# MainBoard.net
KiCad netlist of a schematic drawn in EAGLE
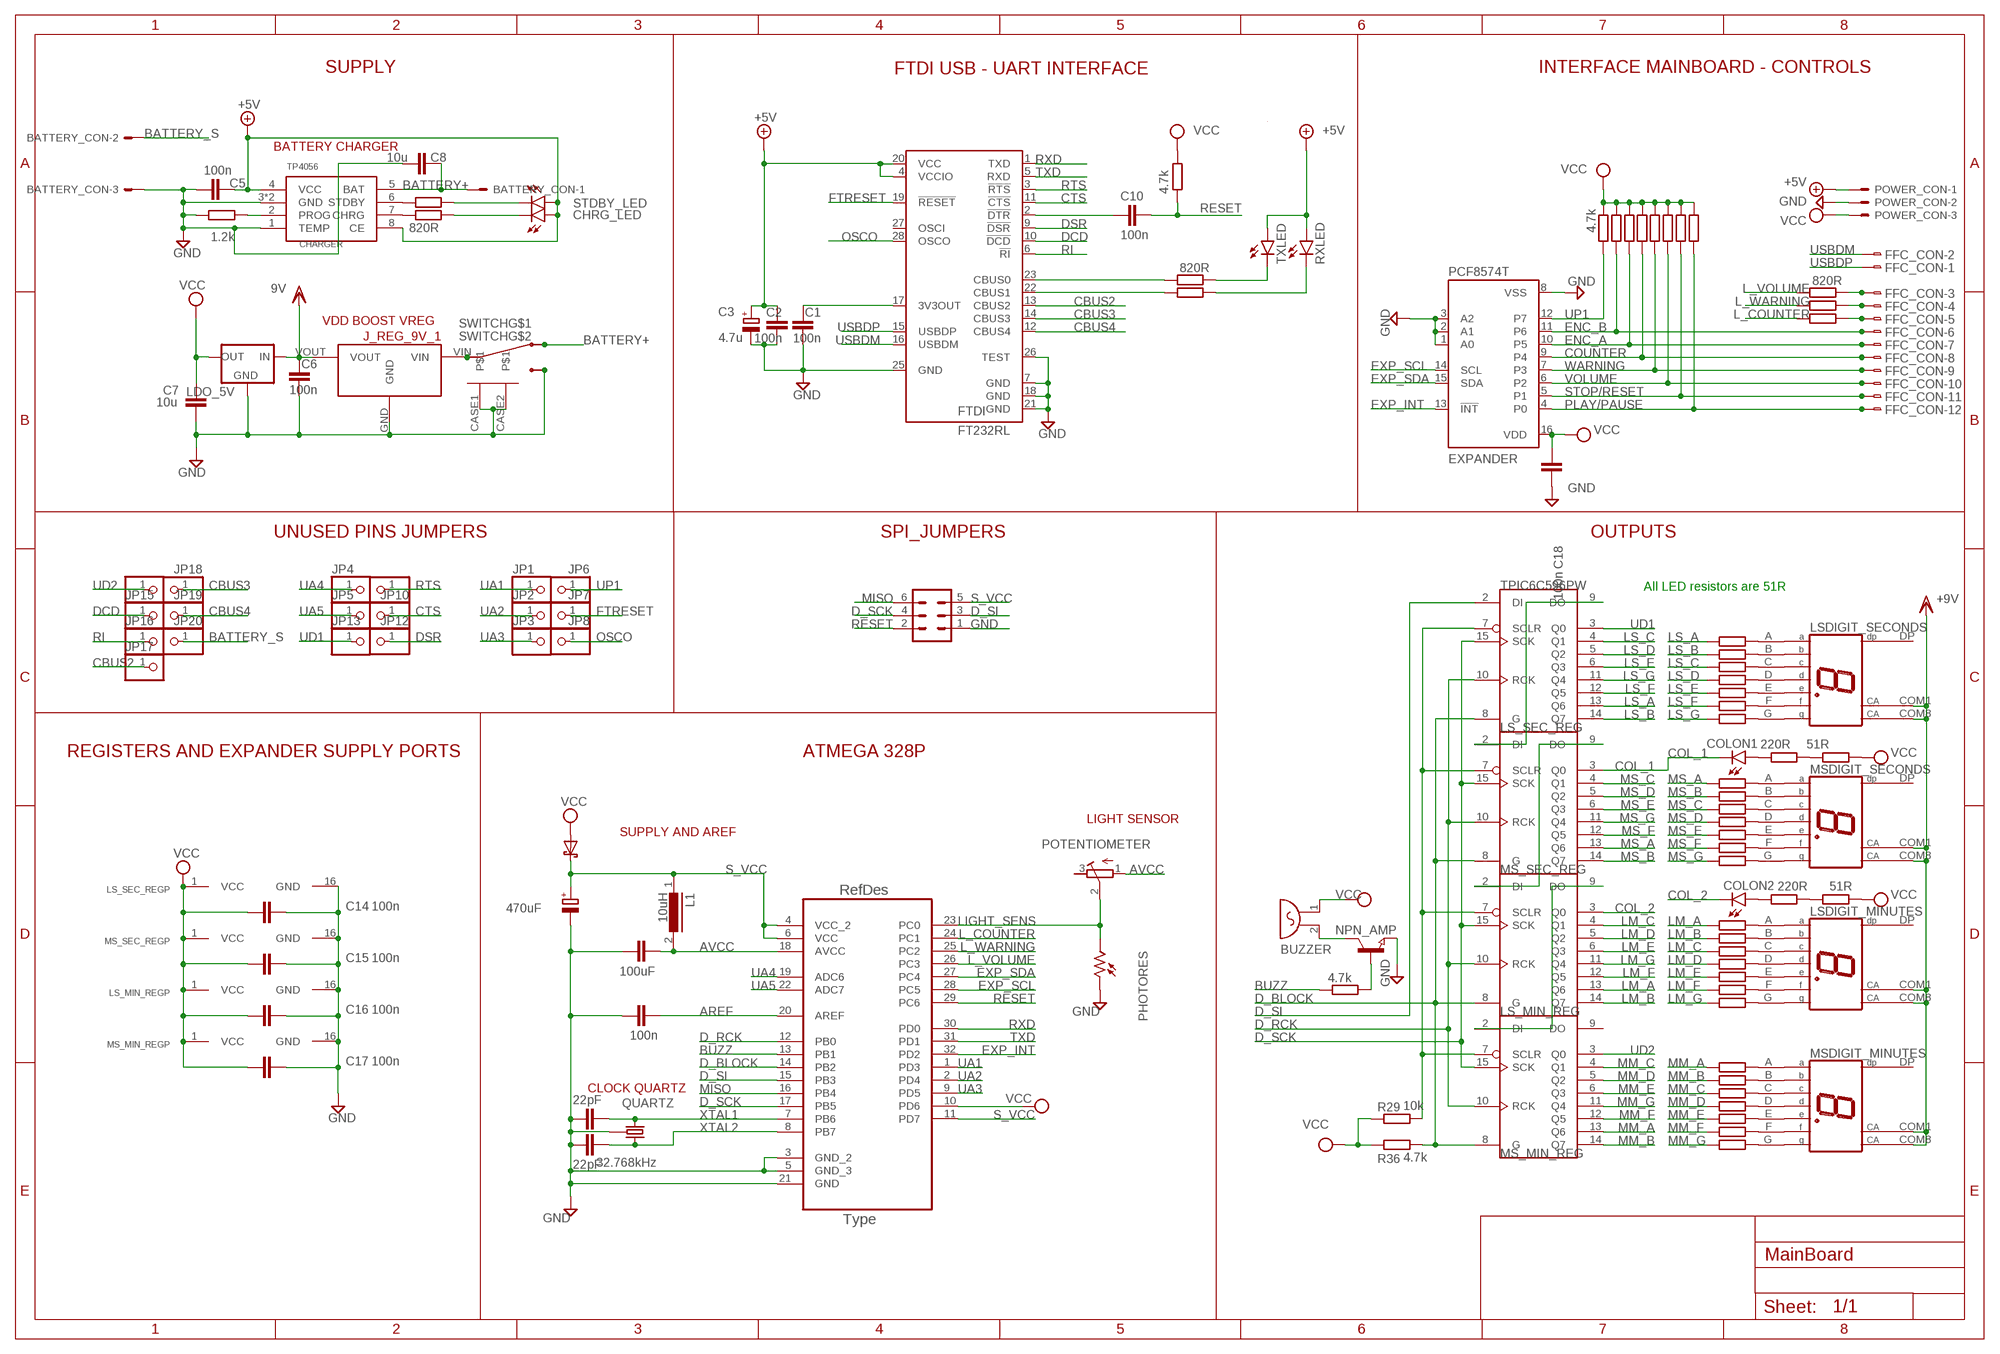
[diagram p0: schematic, sheet 1]

(export (version "E")
  (design (tool "Eeschema 10.0.6"))
  (components
    (comp (ref "ATMEGA328P")
      (value "ATMEGA328P-AU")
      (footprint "eagle-import:QFP80P900X900X120-32N")
      (libsource (lib "eagle-import") (part "ATMEGA328P-AU"))
    )
    (comp (ref "BATTERY_CON")
      (value "JST-XH-03-PIN-LONG-PAD")
      (footprint "eagle-import:JST-XH-03-PACKAGE-LONG-PAD")
      (libsource (lib "eagle-import") (part "JST-XH-03-PIN-LONG-PAD"))
    )
    (comp (ref "BUZZER")
      (value "F/HGP")
      (footprint "eagle-import:F_HGP")
      (libsource (lib "eagle-import") (part "F/HGP"))
    )
    (comp (ref "C1")
      (value "100n")
      (footprint "eagle-import:C0603")
      (libsource (lib "eagle-import") (part "C-EUC0603"))
    )
    (comp (ref "C2")
      (value "100n")
      (footprint "eagle-import:C0603")
      (libsource (lib "eagle-import") (part "C-EUC0603"))
    )
    (comp (ref "C3")
      (value "4.7u")
      (footprint "eagle-import:SMC_B")
      (libsource (lib "eagle-import") (part "CPOL-EUSMCB"))
    )
    (comp (ref "C4")
      (value "100n")
      (footprint "eagle-import:C0603")
      (libsource (lib "eagle-import") (part "C-EUC0603"))
    )
    (comp (ref "C5")
      (value "100n")
      (footprint "eagle-import:C0603")
      (libsource (lib "eagle-import") (part "C-EUC0603"))
    )
    (comp (ref "C6")
      (value "100n")
      (footprint "eagle-import:C0603")
      (libsource (lib "eagle-import") (part "C-EUC0603"))
    )
    (comp (ref "C7")
      (value "10u")
      (footprint "eagle-import:C1206")
      (libsource (lib "eagle-import") (part "C-EUC1206"))
    )
    (comp (ref "C8")
      (value "10u")
      (footprint "eagle-import:C1206")
      (libsource (lib "eagle-import") (part "C-EUC1206"))
    )
    (comp (ref "C10")
      (value "100n")
      (footprint "eagle-import:C0603")
      (libsource (lib "eagle-import") (part "C-EUC0603"))
    )
    (comp (ref "C14")
      (value "100n")
      (footprint "eagle-import:C0603")
      (libsource (lib "eagle-import") (part "C-EUC0603"))
    )
    (comp (ref "C15")
      (value "100n")
      (footprint "eagle-import:C0603")
      (libsource (lib "eagle-import") (part "C-EUC0603"))
    )
    (comp (ref "C16")
      (value "100n")
      (footprint "eagle-import:C0603")
      (libsource (lib "eagle-import") (part "C-EUC0603"))
    )
    (comp (ref "C17")
      (value "100n")
      (footprint "eagle-import:C0603")
      (libsource (lib "eagle-import") (part "C-EUC0603"))
    )
    (comp (ref "C18")
      (value "100n")
      (footprint "eagle-import:C0603")
      (libsource (lib "eagle-import") (part "C-EUC0603"))
    )
    (comp (ref "C29")
      (value "22pF")
      (footprint "eagle-import:C0603")
      (libsource (lib "eagle-import") (part "C-EUC0603"))
    )
    (comp (ref "C30")
      (value "22pF")
      (footprint "eagle-import:C0603")
      (libsource (lib "eagle-import") (part "C-EUC0603"))
    )
    (comp (ref "C31")
      (value "470uF")
      (footprint "eagle-import:153CLV-0810")
      (libsource (lib "eagle-import") (part "CPOL-EU153CLV-0810"))
    )
    (comp (ref "C32")
      (value "100uF")
      (footprint "eagle-import:C1210")
      (libsource (lib "eagle-import") (part "C-EUC1210"))
    )
    (comp (ref "CHARGER")
      (value "TP4056")
      (footprint "eagle-import:SOP-8")
      (libsource (lib "eagle-import") (part "TP4056"))
    )
    (comp (ref "CHRG_LED")
      (value "LEDCHIPLED_0603")
      (footprint "eagle-import:CHIPLED_0603")
      (libsource (lib "eagle-import") (part "led_259_LEDCHIPLED_0603"))
    )
    (comp (ref "COLON1")
      (value "LED5MM")
      (footprint "eagle-import:LED5MM")
      (libsource (lib "eagle-import") (part "LED5MM"))
    )
    (comp (ref "COLON2")
      (value "LED5MM")
      (footprint "eagle-import:LED5MM")
      (libsource (lib "eagle-import") (part "LED5MM"))
    )
    (comp (ref "EXPANDER")
      (value "PCF8574T")
      (footprint "eagle-import:SO16W")
      (fields (field (name "MPN") "PCF8574T/3,512"))
      (libsource (lib "eagle-import") (part "PCF8574T"))
    )
    (comp (ref "FFC_CON")
      (value "FH12-12S-0.5S_THINNER")
      (footprint "eagle-import:FH12-12S-0.5SH_THINER")
      (libsource (lib "eagle-import") (part "FH12-12S-0.5S_THINNER"))
    )
    (comp (ref "FTDI")
      (value "FT232RL")
      (footprint "eagle-import:SSOP28")
      (libsource (lib "eagle-import") (part "FT232RL"))
    )
    (comp (ref "JP1")
      (value "PINHD-1X1")
      (footprint "eagle-import:1X01")
      (libsource (lib "eagle-import") (part "PINHD-1X1"))
    )
    (comp (ref "JP2")
      (value "PINHD-1X1")
      (footprint "eagle-import:1X01")
      (libsource (lib "eagle-import") (part "PINHD-1X1"))
    )
    (comp (ref "JP3")
      (value "PINHD-1X1")
      (footprint "eagle-import:1X01")
      (libsource (lib "eagle-import") (part "PINHD-1X1"))
    )
    (comp (ref "JP4")
      (value "PINHD-1X1")
      (footprint "eagle-import:1X01")
      (libsource (lib "eagle-import") (part "PINHD-1X1"))
    )
    (comp (ref "JP5")
      (value "PINHD-1X1")
      (footprint "eagle-import:1X01")
      (libsource (lib "eagle-import") (part "PINHD-1X1"))
    )
    (comp (ref "JP6")
      (value "PINHD-1X1")
      (footprint "eagle-import:1X01")
      (libsource (lib "eagle-import") (part "PINHD-1X1"))
    )
    (comp (ref "JP7")
      (value "PINHD-1X1")
      (footprint "eagle-import:1X01")
      (libsource (lib "eagle-import") (part "PINHD-1X1"))
    )
    (comp (ref "JP8")
      (value "PINHD-1X1")
      (footprint "eagle-import:1X01")
      (libsource (lib "eagle-import") (part "PINHD-1X1"))
    )
    (comp (ref "JP9")
      (value "PINHD-1X1")
      (footprint "eagle-import:1X01")
      (libsource (lib "eagle-import") (part "PINHD-1X1"))
    )
    (comp (ref "JP10")
      (value "PINHD-1X1")
      (footprint "eagle-import:1X01")
      (libsource (lib "eagle-import") (part "PINHD-1X1"))
    )
    (comp (ref "JP12")
      (value "PINHD-1X1")
      (footprint "eagle-import:1X01")
      (libsource (lib "eagle-import") (part "PINHD-1X1"))
    )
    (comp (ref "JP13")
      (value "PINHD-1X1")
      (footprint "eagle-import:1X01")
      (libsource (lib "eagle-import") (part "PINHD-1X1"))
    )
    (comp (ref "JP14")
      (value "PINHD-1X1")
      (footprint "eagle-import:1X01")
      (libsource (lib "eagle-import") (part "PINHD-1X1"))
    )
    (comp (ref "JP15")
      (value "PINHD-1X1")
      (footprint "eagle-import:1X01")
      (libsource (lib "eagle-import") (part "PINHD-1X1"))
    )
    (comp (ref "JP16")
      (value "PINHD-1X1")
      (footprint "eagle-import:1X01")
      (libsource (lib "eagle-import") (part "PINHD-1X1"))
    )
    (comp (ref "JP17")
      (value "PINHD-1X1")
      (footprint "eagle-import:1X01")
      (libsource (lib "eagle-import") (part "PINHD-1X1"))
    )
    (comp (ref "JP18")
      (value "PINHD-1X1")
      (footprint "eagle-import:1X01")
      (libsource (lib "eagle-import") (part "PINHD-1X1"))
    )
    (comp (ref "JP19")
      (value "PINHD-1X1")
      (footprint "eagle-import:1X01")
      (libsource (lib "eagle-import") (part "PINHD-1X1"))
    )
    (comp (ref "JP20")
      (value "PINHD-1X1")
      (footprint "eagle-import:1X01")
      (libsource (lib "eagle-import") (part "PINHD-1X1"))
    )
    (comp (ref "J_REG_9V_1")
      (value "9V_VOLTAGE_REGULATOR")
      (footprint "eagle-import:9V_VOLTAGE_REGULATOR")
      (libsource (lib "eagle-import") (part "9V_VOLTAGE_REGULATOR"))
    )
    (comp (ref "L1")
      (value "10uH")
      (footprint "eagle-import:DR73")
      (libsource (lib "eagle-import") (part "DR73"))
    )
    (comp (ref "LDO_5V")
      (value "LM1117")
      (footprint "eagle-import:SOT223")
      (libsource (lib "eagle-import") (part "LM1117"))
    )
    (comp (ref "LSDIGIT_MINUTES")
      (value "LED-7-SEGM-56MM")
      (footprint "eagle-import:MYTHT")
      (libsource (lib "eagle-import") (part "LED-7-SEGM-56MM"))
    )
    (comp (ref "LSDIGIT_SECONDS")
      (value "LED-7-SEGM-56MM")
      (footprint "eagle-import:MYTHT")
      (libsource (lib "eagle-import") (part "LED-7-SEGM-56MM"))
    )
    (comp (ref "LS_MIN_REG")
      (value "TPIC6C596PW")
      (footprint "eagle-import:SO16")
      (libsource (lib "eagle-import") (part "TPIC6C596PW"))
    )
    (comp (ref "LS_SEC_REG")
      (value "TPIC6C596PW")
      (footprint "eagle-import:SO16")
      (libsource (lib "eagle-import") (part "TPIC6C596PW"))
    )
    (comp (ref "MSDIGIT_MINUTES")
      (value "LED-7-SEGM-56MM")
      (footprint "eagle-import:MYTHT")
      (libsource (lib "eagle-import") (part "LED-7-SEGM-56MM"))
    )
    (comp (ref "MSDIGIT_SECONDS")
      (value "LED-7-SEGM-56MM")
      (footprint "eagle-import:MYTHT")
      (libsource (lib "eagle-import") (part "LED-7-SEGM-56MM"))
    )
    (comp (ref "MS_MIN_REG")
      (value "TPIC6C596PW")
      (footprint "eagle-import:SO16")
      (libsource (lib "eagle-import") (part "TPIC6C596PW"))
    )
    (comp (ref "MS_SEC_REG")
      (value "TPIC6C596PW")
      (footprint "eagle-import:SO16")
      (libsource (lib "eagle-import") (part "TPIC6C596PW"))
    )
    (comp (ref "NPN_AMP")
      (value "NPN-TRANSISTOR_SOT23")
      (footprint "eagle-import:SOT23")
      (libsource (lib "eagle-import") (part "NPN-TRANSISTOR_SOT23"))
    )
    (comp (ref "PHOTORES")
      (value "VT90N1")
      (footprint "eagle-import:VT900")
      (fields (field (name "SPICEPREFIX") "B"))
      (libsource (lib "eagle-import") (part "VT90N1"))
    )
    (comp (ref "POTENTIOMETER")
      (value "R-TRIMM3296Y")
      (footprint "eagle-import:RTRIM3296Y")
      (libsource (lib "eagle-import") (part "R-TRIMM3296Y"))
    )
    (comp (ref "POWER_CON")
      (value "JST-XH-03-PIN-LONG-PAD")
      (footprint "eagle-import:JST-XH-03-PACKAGE-LONG-PAD")
      (libsource (lib "eagle-import") (part "JST-XH-03-PIN-LONG-PAD"))
    )
    (comp (ref "QUARTZ")
      (value "32.768kHz")
      (footprint "eagle-import:CRYSTAL-SMD-2X6-CYL")
      (libsource (lib "eagle-import") (part "CRYSTAL-32.768KHZ_GNDSMD-2X6"))
    )
    (comp (ref "R1")
      (value "50")
      (footprint "eagle-import:R0603")
      (libsource (lib "eagle-import") (part "R-EU_R0603"))
    )
    (comp (ref "R2")
      (value "50")
      (footprint "eagle-import:R0603")
      (libsource (lib "eagle-import") (part "R-EU_R0603"))
    )
    (comp (ref "R3")
      (value "50")
      (footprint "eagle-import:R0603")
      (libsource (lib "eagle-import") (part "R-EU_R0603"))
    )
    (comp (ref "R4")
      (value "50")
      (footprint "eagle-import:R0603")
      (libsource (lib "eagle-import") (part "R-EU_R0603"))
    )
    (comp (ref "R5")
      (value "50")
      (footprint "eagle-import:R0603")
      (libsource (lib "eagle-import") (part "R-EU_R0603"))
    )
    (comp (ref "R6")
      (value "50")
      (footprint "eagle-import:R0603")
      (libsource (lib "eagle-import") (part "R-EU_R0603"))
    )
    (comp (ref "R7")
      (value "50")
      (footprint "eagle-import:R0603")
      (libsource (lib "eagle-import") (part "R-EU_R0603"))
    )
    (comp (ref "R8")
      (value "50")
      (footprint "eagle-import:R0603")
      (libsource (lib "eagle-import") (part "R-EU_R0603"))
    )
    (comp (ref "R9")
      (value "50")
      (footprint "eagle-import:R0603")
      (libsource (lib "eagle-import") (part "R-EU_R0603"))
    )
    (comp (ref "R10")
      (value "50")
      (footprint "eagle-import:R0603")
      (libsource (lib "eagle-import") (part "R-EU_R0603"))
    )
    (comp (ref "R11")
      (value "50")
      (footprint "eagle-import:R0603")
      (libsource (lib "eagle-import") (part "R-EU_R0603"))
    )
    (comp (ref "R12")
      (value "50")
      (footprint "eagle-import:R0603")
      (libsource (lib "eagle-import") (part "R-EU_R0603"))
    )
    (comp (ref "R13")
      (value "50")
      (footprint "eagle-import:R0603")
      (libsource (lib "eagle-import") (part "R-EU_R0603"))
    )
    (comp (ref "R14")
      (value "50")
      (footprint "eagle-import:R0603")
      (libsource (lib "eagle-import") (part "R-EU_R0603"))
    )
    (comp (ref "R15")
      (value "50")
      (footprint "eagle-import:R0603")
      (libsource (lib "eagle-import") (part "R-EU_R0603"))
    )
    (comp (ref "R16")
      (value "50")
      (footprint "eagle-import:R0603")
      (libsource (lib "eagle-import") (part "R-EU_R0603"))
    )
    (comp (ref "R17")
      (value "50")
      (footprint "eagle-import:R0603")
      (libsource (lib "eagle-import") (part "R-EU_R0603"))
    )
    (comp (ref "R18")
      (value "50")
      (footprint "eagle-import:R0603")
      (libsource (lib "eagle-import") (part "R-EU_R0603"))
    )
    (comp (ref "R19")
      (value "50")
      (footprint "eagle-import:R0603")
      (libsource (lib "eagle-import") (part "R-EU_R0603"))
    )
    (comp (ref "R20")
      (value "50")
      (footprint "eagle-import:R0603")
      (libsource (lib "eagle-import") (part "R-EU_R0603"))
    )
    (comp (ref "R21")
      (value "50")
      (footprint "eagle-import:R0603")
      (libsource (lib "eagle-import") (part "R-EU_R0603"))
    )
    (comp (ref "R22")
      (value "50")
      (footprint "eagle-import:R0603")
      (libsource (lib "eagle-import") (part "R-EU_R0603"))
    )
    (comp (ref "R23")
      (value "50")
      (footprint "eagle-import:R0603")
      (libsource (lib "eagle-import") (part "R-EU_R0603"))
    )
    (comp (ref "R24")
      (value "50")
      (footprint "eagle-import:R0603")
      (libsource (lib "eagle-import") (part "R-EU_R0603"))
    )
    (comp (ref "R25")
      (value "50")
      (footprint "eagle-import:R0603")
      (libsource (lib "eagle-import") (part "R-EU_R0603"))
    )
    (comp (ref "R26")
      (value "50")
      (footprint "eagle-import:R0603")
      (libsource (lib "eagle-import") (part "R-EU_R0603"))
    )
    (comp (ref "R27")
      (value "50")
      (footprint "eagle-import:R0603")
      (libsource (lib "eagle-import") (part "R-EU_R0603"))
    )
    (comp (ref "R28")
      (value "50")
      (footprint "eagle-import:R0603")
      (libsource (lib "eagle-import") (part "R-EU_R0603"))
    )
    (comp (ref "R29")
      (value "10k")
      (footprint "eagle-import:R0603")
      (libsource (lib "eagle-import") (part "R-EU_R0603"))
    )
    (comp (ref "R30")
      (value "4.7k")
      (footprint "eagle-import:R0603")
      (libsource (lib "eagle-import") (part "R-EU_R0603"))
    )
    (comp (ref "R31")
      (value "4.7k")
      (footprint "eagle-import:R0603")
      (libsource (lib "eagle-import") (part "R-EU_R0603"))
    )
    (comp (ref "R32")
      (value "51R")
      (footprint "eagle-import:R0603")
      (libsource (lib "eagle-import") (part "R-EU_R0603"))
    )
    (comp (ref "R33")
      (value "4.7k")
      (footprint "eagle-import:R0603")
      (libsource (lib "eagle-import") (part "R-EU_R0603"))
    )
    (comp (ref "R34")
      (value "220R")
      (footprint "eagle-import:R0603")
      (libsource (lib "eagle-import") (part "R-EU_R0603"))
    )
    (comp (ref "R35")
      (value "51R")
      (footprint "eagle-import:R0603")
      (libsource (lib "eagle-import") (part "R-EU_R0603"))
    )
    (comp (ref "R36")
      (value "4.7k")
      (footprint "eagle-import:R0603")
      (libsource (lib "eagle-import") (part "R-EU_R0603"))
    )
    (comp (ref "R39")
      (value "820R")
      (footprint "eagle-import:R0603")
      (libsource (lib "eagle-import") (part "R-EU_R0603"))
    )
    (comp (ref "R40")
      (value "820R")
      (footprint "eagle-import:R0603")
      (libsource (lib "eagle-import") (part "R-EU_R0603"))
    )
    (comp (ref "R42")
      (value "4.7k")
      (footprint "eagle-import:R0603")
      (libsource (lib "eagle-import") (part "R-EU_R0603"))
    )
    (comp (ref "R43")
      (value "4.7k")
      (footprint "eagle-import:R0603")
      (libsource (lib "eagle-import") (part "R-EU_R0603"))
    )
    (comp (ref "R44")
      (value "4.7k")
      (footprint "eagle-import:R0603")
      (libsource (lib "eagle-import") (part "R-EU_R0603"))
    )
    (comp (ref "R45")
      (value "4.7k")
      (footprint "eagle-import:R0603")
      (libsource (lib "eagle-import") (part "R-EU_R0603"))
    )
    (comp (ref "R46")
      (value "4.7k")
      (footprint "eagle-import:R0603")
      (libsource (lib "eagle-import") (part "R-EU_R0603"))
    )
    (comp (ref "R47")
      (value "820R")
      (footprint "eagle-import:R0603")
      (libsource (lib "eagle-import") (part "R-EU_R0603"))
    )
    (comp (ref "R48")
      (value "1.2k")
      (footprint "eagle-import:R0603")
      (libsource (lib "eagle-import") (part "R-EU_R0603"))
    )
    (comp (ref "R50")
      (value "220R")
      (footprint "eagle-import:R0603")
      (libsource (lib "eagle-import") (part "R-EU_R0603"))
    )
    (comp (ref "R52")
      (value "820R")
      (footprint "eagle-import:R0603")
      (libsource (lib "eagle-import") (part "R-EU_R0603"))
    )
    (comp (ref "R56")
      (value "4.7k")
      (footprint "eagle-import:R0603")
      (libsource (lib "eagle-import") (part "R-EU_R0603"))
    )
    (comp (ref "R61")
      (value "4.7k")
      (footprint "eagle-import:R0603")
      (libsource (lib "eagle-import") (part "R-EU_R0603"))
    )
    (comp (ref "R64")
      (value "820R")
      (footprint "eagle-import:R0603")
      (libsource (lib "eagle-import") (part "R-EU_R0603"))
    )
    (comp (ref "R65")
      (value "820R")
      (footprint "eagle-import:R0603")
      (libsource (lib "eagle-import") (part "R-EU_R0603"))
    )
    (comp (ref "R66")
      (value "820R")
      (footprint "eagle-import:R0603")
      (libsource (lib "eagle-import") (part "R-EU_R0603"))
    )
    (comp (ref "RXLED")
      (value "LEDCHIPLED_0603")
      (footprint "eagle-import:CHIPLED_0603")
      (libsource (lib "eagle-import") (part "led_259_LEDCHIPLED_0603"))
    )
    (comp (ref "SHOTTKY")
      (value "S2A")
      (footprint "eagle-import:DO214AA")
      (fields (field (name "MF") "Fairchild"))
      (libsource (lib "eagle-import") (part "S2A"))
    )
    (comp (ref "SPI_JUMPERS")
      (value "MA03-2")
      (footprint "eagle-import:MA03-2")
      (libsource (lib "eagle-import") (part "MA03-2"))
    )
    (comp (ref "STDBY_LED")
      (value "LEDCHIPLED_0603")
      (footprint "eagle-import:CHIPLED_0603")
      (libsource (lib "eagle-import") (part "led_259_LEDCHIPLED_0603"))
    )
    (comp (ref "SWITCH")
      (value "X2")
      (footprint "eagle-import:MINI")
      (libsource (lib "eagle-import") (part "X2"))
    )
    (comp (ref "TXLED")
      (value "LEDCHIPLED_0603")
      (footprint "eagle-import:CHIPLED_0603")
      (libsource (lib "eagle-import") (part "led_259_LEDCHIPLED_0603"))
    )
  )
  (nets
    (net (code "1") (name "+5V") (class "Default")
      (node (ref "C2") (pin "2") (pinfunction "2_2") (pintype "passive"))
      (node (ref "C3") (pin "+") (pinfunction "+_+") (pintype "passive"))
      (node (ref "C5") (pin "1") (pinfunction "1_1") (pintype "passive"))
      (node (ref "CHARGER") (pin "4") (pinfunction "VCC_4") (pintype "bidirectional"))
      (node (ref "CHARGER") (pin "8") (pinfunction "CE_8") (pintype "bidirectional"))
      (node (ref "CHRG_LED") (pin "A") (pinfunction "A_A") (pintype "passive"))
      (node (ref "FTDI") (pin "20") (pinfunction "VCC_20") (pintype "power_in"))
      (node (ref "FTDI") (pin "4") (pinfunction "VCCIO_4") (pintype "power_in"))
      (node (ref "POWER_CON") (pin "1") (pinfunction "S_1") (pintype "passive"))
      (node (ref "RXLED") (pin "A") (pinfunction "A_A") (pintype "passive"))
      (node (ref "STDBY_LED") (pin "A") (pinfunction "A_A") (pintype "passive"))
      (node (ref "TXLED") (pin "A") (pinfunction "A_A") (pintype "passive"))
    )
    (net (code "2") (name "+9V") (class "Default")
      (node (ref "C6") (pin "2") (pinfunction "2_2") (pintype "passive"))
      (node (ref "J_REG_9V_1") (pin "VOUT") (pinfunction "VOUT_VOUT") (pintype "bidirectional"))
      (node (ref "LDO_5V") (pin "3") (pinfunction "IN_3") (pintype "input"))
      (node (ref "LSDIGIT_MINUTES") (pin "COM1") (pinfunction "CA1_COM1") (pintype "passive"))
      (node (ref "LSDIGIT_MINUTES") (pin "COM8") (pinfunction "CA8_COM8") (pintype "passive"))
      (node (ref "LSDIGIT_SECONDS") (pin "COM1") (pinfunction "CA1_COM1") (pintype "passive"))
      (node (ref "LSDIGIT_SECONDS") (pin "COM8") (pinfunction "CA8_COM8") (pintype "passive"))
      (node (ref "MSDIGIT_MINUTES") (pin "COM1") (pinfunction "CA1_COM1") (pintype "passive"))
      (node (ref "MSDIGIT_MINUTES") (pin "COM8") (pinfunction "CA8_COM8") (pintype "passive"))
      (node (ref "MSDIGIT_SECONDS") (pin "COM1") (pinfunction "CA1_COM1") (pintype "passive"))
      (node (ref "MSDIGIT_SECONDS") (pin "COM8") (pinfunction "CA8_COM8") (pintype "passive"))
    )
    (net (code "3") (name "/AREF") (class "Default")
      (node (ref "ATMEGA328P") (pin "20") (pinfunction "AREF_20") (pintype "input"))
      (node (ref "C4") (pin "1") (pinfunction "1_1") (pintype "passive"))
    )
    (net (code "4") (name "/AVCC") (class "Default")
      (node (ref "ATMEGA328P") (pin "18") (pinfunction "AVCC_18") (pintype "power_in"))
      (node (ref "C32") (pin "1") (pinfunction "1_1") (pintype "passive"))
      (node (ref "L1") (pin "2") (pinfunction "2_2") (pintype "passive"))
      (node (ref "POTENTIOMETER") (pin "1") (pinfunction "A_1") (pintype "passive"))
    )
    (net (code "5") (name "/BATTERY+") (class "Default")
      (node (ref "BATTERY_CON") (pin "1") (pinfunction "S_1") (pintype "passive"))
      (node (ref "C8") (pin "2") (pinfunction "2_2") (pintype "passive"))
      (node (ref "CHARGER") (pin "5") (pinfunction "BAT_5") (pintype "bidirectional"))
      (node (ref "SWITCH") (pin "1") (pinfunction "P$1_1") (pintype "bidirectional"))
      (node (ref "SWITCH") (pin "4") (pinfunction "P$1_4") (pintype "bidirectional"))
    )
    (net (code "6") (name "/BATTERY_S") (class "Default")
      (node (ref "BATTERY_CON") (pin "2") (pinfunction "S_2") (pintype "passive"))
      (node (ref "JP20") (pin "1") (pinfunction "1_1") (pintype "passive"))
    )
    (net (code "7") (name "/BUZZ") (class "Default")
      (node (ref "ATMEGA328P") (pin "13") (pinfunction "PB1_13") (pintype "bidirectional"))
      (node (ref "R30") (pin "2") (pinfunction "2_2") (pintype "passive"))
    )
    (net (code "8") (name "/CBUS2") (class "Default")
      (node (ref "FTDI") (pin "13") (pinfunction "CBUS2_13") (pintype "bidirectional"))
      (node (ref "JP17") (pin "1") (pinfunction "1_1") (pintype "passive"))
    )
    (net (code "9") (name "/CBUS3") (class "Default")
      (node (ref "FTDI") (pin "14") (pinfunction "CBUS3_14") (pintype "bidirectional"))
      (node (ref "JP18") (pin "1") (pinfunction "1_1") (pintype "passive"))
    )
    (net (code "10") (name "/CBUS4") (class "Default")
      (node (ref "FTDI") (pin "12") (pinfunction "CBUS4_12") (pintype "bidirectional"))
      (node (ref "JP19") (pin "1") (pinfunction "1_1") (pintype "passive"))
    )
    (net (code "11") (name "/COL_1") (class "Default")
      (node (ref "COLON1") (pin "K") (pinfunction "C_K") (pintype "passive"))
      (node (ref "MS_SEC_REG") (pin "3") (pinfunction "Q0_3") (pintype "open_collector"))
    )
    (net (code "12") (name "/COL_2") (class "Default")
      (node (ref "COLON2") (pin "K") (pinfunction "C_K") (pintype "passive"))
      (node (ref "LS_MIN_REG") (pin "3") (pinfunction "Q0_3") (pintype "open_collector"))
    )
    (net (code "13") (name "/COUNTER") (class "Default")
      (node (ref "EXPANDER") (pin "9") (pinfunction "P4_9") (pintype "bidirectional"))
      (node (ref "FFC_CON") (pin "8") (pinfunction "1_8") (pintype "passive"))
      (node (ref "R42") (pin "2") (pinfunction "2_2") (pintype "passive"))
    )
    (net (code "14") (name "/CTS") (class "Default")
      (node (ref "FTDI") (pin "11") (pinfunction "~{CTS}_11") (pintype "input"))
      (node (ref "JP10") (pin "1") (pinfunction "1_1") (pintype "passive"))
    )
    (net (code "15") (name "/DCD") (class "Default")
      (node (ref "FTDI") (pin "10") (pinfunction "~{DCD}_10") (pintype "input"))
      (node (ref "JP15") (pin "1") (pinfunction "1_1") (pintype "passive"))
    )
    (net (code "16") (name "/DSR") (class "Default")
      (node (ref "FTDI") (pin "9") (pinfunction "~{DSR}_9") (pintype "input"))
      (node (ref "JP12") (pin "1") (pinfunction "1_1") (pintype "passive"))
    )
    (net (code "17") (name "/D_BLOCK") (class "Default")
      (node (ref "ATMEGA328P") (pin "14") (pinfunction "PB2_14") (pintype "bidirectional"))
      (node (ref "LS_MIN_REG") (pin "8") (pinfunction "G_8") (pintype "input"))
      (node (ref "LS_SEC_REG") (pin "8") (pinfunction "G_8") (pintype "input"))
      (node (ref "MS_MIN_REG") (pin "8") (pinfunction "G_8") (pintype "input"))
      (node (ref "MS_SEC_REG") (pin "8") (pinfunction "G_8") (pintype "input"))
      (node (ref "R36") (pin "1") (pinfunction "1_1") (pintype "passive"))
    )
    (net (code "18") (name "/D_RCK") (class "Default")
      (node (ref "ATMEGA328P") (pin "12") (pinfunction "PB0_12") (pintype "bidirectional"))
      (node (ref "LS_MIN_REG") (pin "10") (pinfunction "RCK_10") (pintype "input"))
      (node (ref "LS_SEC_REG") (pin "10") (pinfunction "RCK_10") (pintype "input"))
      (node (ref "MS_MIN_REG") (pin "10") (pinfunction "RCK_10") (pintype "input"))
      (node (ref "MS_SEC_REG") (pin "10") (pinfunction "RCK_10") (pintype "input"))
    )
    (net (code "19") (name "/D_SCK") (class "Default")
      (node (ref "ATMEGA328P") (pin "17") (pinfunction "PB5_17") (pintype "bidirectional"))
      (node (ref "LS_MIN_REG") (pin "15") (pinfunction "SCK_15") (pintype "input"))
      (node (ref "LS_SEC_REG") (pin "15") (pinfunction "SCK_15") (pintype "input"))
      (node (ref "MS_MIN_REG") (pin "15") (pinfunction "SCK_15") (pintype "input"))
      (node (ref "MS_SEC_REG") (pin "15") (pinfunction "SCK_15") (pintype "input"))
      (node (ref "SPI_JUMPERS") (pin "4") (pinfunction "4_4") (pintype "passive"))
    )
    (net (code "20") (name "/D_SI") (class "Default")
      (node (ref "ATMEGA328P") (pin "15") (pinfunction "PB3_15") (pintype "bidirectional"))
      (node (ref "LS_SEC_REG") (pin "2") (pinfunction "DI_2") (pintype "input"))
      (node (ref "SPI_JUMPERS") (pin "3") (pinfunction "3_3") (pintype "passive"))
    )
    (net (code "21") (name "/ENC_A") (class "Default")
      (node (ref "EXPANDER") (pin "10") (pinfunction "P5_10") (pintype "bidirectional"))
      (node (ref "FFC_CON") (pin "7") (pinfunction "1_7") (pintype "passive"))
      (node (ref "R33") (pin "2") (pinfunction "2_2") (pintype "passive"))
    )
    (net (code "22") (name "/ENC_B") (class "Default")
      (node (ref "EXPANDER") (pin "11") (pinfunction "P6_11") (pintype "bidirectional"))
      (node (ref "FFC_CON") (pin "6") (pinfunction "1_6") (pintype "passive"))
      (node (ref "R31") (pin "2") (pinfunction "2_2") (pintype "passive"))
    )
    (net (code "23") (name "/EXP_INT") (class "Default")
      (node (ref "ATMEGA328P") (pin "32") (pinfunction "PD2_32") (pintype "bidirectional"))
      (node (ref "EXPANDER") (pin "13") (pinfunction "~{INT}_13") (pintype "output"))
    )
    (net (code "24") (name "/EXP_SCL") (class "Default")
      (node (ref "ATMEGA328P") (pin "28") (pinfunction "PC5_28") (pintype "bidirectional"))
      (node (ref "EXPANDER") (pin "14") (pinfunction "SCL_14") (pintype "input"))
    )
    (net (code "25") (name "/EXP_SDA") (class "Default")
      (node (ref "ATMEGA328P") (pin "27") (pinfunction "PC4_27") (pintype "bidirectional"))
      (node (ref "EXPANDER") (pin "15") (pinfunction "SDA_15") (pintype "bidirectional"))
    )
    (net (code "26") (name "/FTRESET") (class "Default")
      (node (ref "FTDI") (pin "19") (pinfunction "~{RESET}_19") (pintype "input"))
      (node (ref "JP7") (pin "1") (pinfunction "1_1") (pintype "passive"))
    )
    (net (code "27") (name "/LIGHT_SENS") (class "Default")
      (node (ref "ATMEGA328P") (pin "23") (pinfunction "PC0_23") (pintype "bidirectional"))
      (node (ref "PHOTORES") (pin "2") (pinfunction "2_2") (pintype "passive"))
      (node (ref "POTENTIOMETER") (pin "2") (pinfunction "S_2") (pintype "passive"))
    )
    (net (code "28") (name "/LM_A") (class "Default")
      (node (ref "LS_MIN_REG") (pin "13") (pinfunction "Q6_13") (pintype "open_collector"))
      (node (ref "R7") (pin "2") (pinfunction "2_2") (pintype "passive"))
    )
    (net (code "29") (name "/LM_B") (class "Default")
      (node (ref "LS_MIN_REG") (pin "14") (pinfunction "Q7_14") (pintype "open_collector"))
      (node (ref "R6") (pin "2") (pinfunction "2_2") (pintype "passive"))
    )
    (net (code "30") (name "/LM_C") (class "Default")
      (node (ref "LS_MIN_REG") (pin "4") (pinfunction "Q1_4") (pintype "open_collector"))
      (node (ref "R5") (pin "2") (pinfunction "2_2") (pintype "passive"))
    )
    (net (code "31") (name "/LM_D") (class "Default")
      (node (ref "LS_MIN_REG") (pin "5") (pinfunction "Q2_5") (pintype "open_collector"))
      (node (ref "R4") (pin "2") (pinfunction "2_2") (pintype "passive"))
    )
    (net (code "32") (name "/LM_E") (class "Default")
      (node (ref "LS_MIN_REG") (pin "6") (pinfunction "Q3_6") (pintype "open_collector"))
      (node (ref "R3") (pin "2") (pinfunction "2_2") (pintype "passive"))
    )
    (net (code "33") (name "/LM_F") (class "Default")
      (node (ref "LS_MIN_REG") (pin "12") (pinfunction "Q5_12") (pintype "open_collector"))
      (node (ref "R2") (pin "2") (pinfunction "2_2") (pintype "passive"))
    )
    (net (code "34") (name "/LM_G") (class "Default")
      (node (ref "LS_MIN_REG") (pin "11") (pinfunction "Q4_11") (pintype "open_collector"))
      (node (ref "R1") (pin "2") (pinfunction "2_2") (pintype "passive"))
    )
    (net (code "35") (name "/LS_A") (class "Default")
      (node (ref "LS_SEC_REG") (pin "13") (pinfunction "Q6_13") (pintype "open_collector"))
      (node (ref "R21") (pin "2") (pinfunction "2_2") (pintype "passive"))
    )
    (net (code "36") (name "/LS_B") (class "Default")
      (node (ref "LS_SEC_REG") (pin "14") (pinfunction "Q7_14") (pintype "open_collector"))
      (node (ref "R20") (pin "2") (pinfunction "2_2") (pintype "passive"))
    )
    (net (code "37") (name "/LS_C") (class "Default")
      (node (ref "LS_SEC_REG") (pin "4") (pinfunction "Q1_4") (pintype "open_collector"))
      (node (ref "R19") (pin "2") (pinfunction "2_2") (pintype "passive"))
    )
    (net (code "38") (name "/LS_D") (class "Default")
      (node (ref "LS_SEC_REG") (pin "5") (pinfunction "Q2_5") (pintype "open_collector"))
      (node (ref "R18") (pin "2") (pinfunction "2_2") (pintype "passive"))
    )
    (net (code "39") (name "/LS_E") (class "Default")
      (node (ref "LS_SEC_REG") (pin "6") (pinfunction "Q3_6") (pintype "open_collector"))
      (node (ref "R17") (pin "2") (pinfunction "2_2") (pintype "passive"))
    )
    (net (code "40") (name "/LS_F") (class "Default")
      (node (ref "LS_SEC_REG") (pin "12") (pinfunction "Q5_12") (pintype "open_collector"))
      (node (ref "R16") (pin "2") (pinfunction "2_2") (pintype "passive"))
    )
    (net (code "41") (name "/LS_G") (class "Default")
      (node (ref "LS_SEC_REG") (pin "11") (pinfunction "Q4_11") (pintype "open_collector"))
      (node (ref "R15") (pin "2") (pinfunction "2_2") (pintype "passive"))
    )
    (net (code "42") (name "/L_COUNTER") (class "Default")
      (node (ref "ATMEGA328P") (pin "24") (pinfunction "PC1_24") (pintype "bidirectional"))
      (node (ref "R52") (pin "2") (pinfunction "2_2") (pintype "passive"))
    )
    (net (code "43") (name "/L_VOLUME") (class "Default")
      (node (ref "ATMEGA328P") (pin "26") (pinfunction "PC3_26") (pintype "bidirectional"))
      (node (ref "R64") (pin "2") (pinfunction "2_2") (pintype "passive"))
    )
    (net (code "44") (name "/L_WARNING") (class "Default")
      (node (ref "ATMEGA328P") (pin "25") (pinfunction "PC2_25") (pintype "bidirectional"))
      (node (ref "R47") (pin "2") (pinfunction "2_2") (pintype "passive"))
    )
    (net (code "45") (name "/MISO") (class "Default")
      (node (ref "ATMEGA328P") (pin "16") (pinfunction "PB4_16") (pintype "bidirectional"))
      (node (ref "SPI_JUMPERS") (pin "6") (pinfunction "6_6") (pintype "passive"))
    )
    (net (code "46") (name "/MM_A") (class "Default")
      (node (ref "MS_MIN_REG") (pin "13") (pinfunction "Q6_13") (pintype "open_collector"))
      (node (ref "R27") (pin "2") (pinfunction "2_2") (pintype "passive"))
    )
    (net (code "47") (name "/MM_B") (class "Default")
      (node (ref "MS_MIN_REG") (pin "14") (pinfunction "Q7_14") (pintype "open_collector"))
      (node (ref "R26") (pin "2") (pinfunction "2_2") (pintype "passive"))
    )
    (net (code "48") (name "/MM_C") (class "Default")
      (node (ref "MS_MIN_REG") (pin "4") (pinfunction "Q1_4") (pintype "open_collector"))
      (node (ref "R25") (pin "2") (pinfunction "2_2") (pintype "passive"))
    )
    (net (code "49") (name "/MM_D") (class "Default")
      (node (ref "MS_MIN_REG") (pin "5") (pinfunction "Q2_5") (pintype "open_collector"))
      (node (ref "R24") (pin "2") (pinfunction "2_2") (pintype "passive"))
    )
    (net (code "50") (name "/MM_E") (class "Default")
      (node (ref "MS_MIN_REG") (pin "6") (pinfunction "Q3_6") (pintype "open_collector"))
      (node (ref "R23") (pin "2") (pinfunction "2_2") (pintype "passive"))
    )
    (net (code "51") (name "/MM_F") (class "Default")
      (node (ref "MS_MIN_REG") (pin "12") (pinfunction "Q5_12") (pintype "open_collector"))
      (node (ref "R22") (pin "2") (pinfunction "2_2") (pintype "passive"))
    )
    (net (code "52") (name "/MM_G") (class "Default")
      (node (ref "MS_MIN_REG") (pin "11") (pinfunction "Q4_11") (pintype "open_collector"))
      (node (ref "R28") (pin "2") (pinfunction "2_2") (pintype "passive"))
    )
    (net (code "53") (name "/MS_A") (class "Default")
      (node (ref "MS_SEC_REG") (pin "13") (pinfunction "Q6_13") (pintype "open_collector"))
      (node (ref "R14") (pin "2") (pinfunction "2_2") (pintype "passive"))
    )
    (net (code "54") (name "/MS_B") (class "Default")
      (node (ref "MS_SEC_REG") (pin "14") (pinfunction "Q7_14") (pintype "open_collector"))
      (node (ref "R13") (pin "2") (pinfunction "2_2") (pintype "passive"))
    )
    (net (code "55") (name "/MS_C") (class "Default")
      (node (ref "MS_SEC_REG") (pin "4") (pinfunction "Q1_4") (pintype "open_collector"))
      (node (ref "R12") (pin "2") (pinfunction "2_2") (pintype "passive"))
    )
    (net (code "56") (name "/MS_D") (class "Default")
      (node (ref "MS_SEC_REG") (pin "5") (pinfunction "Q2_5") (pintype "open_collector"))
      (node (ref "R11") (pin "2") (pinfunction "2_2") (pintype "passive"))
    )
    (net (code "57") (name "/MS_E") (class "Default")
      (node (ref "MS_SEC_REG") (pin "6") (pinfunction "Q3_6") (pintype "open_collector"))
      (node (ref "R10") (pin "2") (pinfunction "2_2") (pintype "passive"))
    )
    (net (code "58") (name "/MS_F") (class "Default")
      (node (ref "MS_SEC_REG") (pin "12") (pinfunction "Q5_12") (pintype "open_collector"))
      (node (ref "R9") (pin "2") (pinfunction "2_2") (pintype "passive"))
    )
    (net (code "59") (name "/MS_G") (class "Default")
      (node (ref "MS_SEC_REG") (pin "11") (pinfunction "Q4_11") (pintype "open_collector"))
      (node (ref "R8") (pin "2") (pinfunction "2_2") (pintype "passive"))
    )
    (net (code "60") (name "/OSCO") (class "Default")
      (node (ref "FTDI") (pin "28") (pinfunction "OSCO_28") (pintype "output"))
      (node (ref "JP8") (pin "1") (pinfunction "1_1") (pintype "passive"))
    )
    (net (code "61") (name "/PLAY{slash}PAUSE") (class "Default")
      (node (ref "EXPANDER") (pin "4") (pinfunction "P0_4") (pintype "bidirectional"))
      (node (ref "FFC_CON") (pin "12") (pinfunction "1_12") (pintype "passive"))
      (node (ref "R46") (pin "2") (pinfunction "2_2") (pintype "passive"))
    )
    (net (code "62") (name "/RESET") (class "Default")
      (node (ref "ATMEGA328P") (pin "29") (pinfunction "PC6_29") (pintype "bidirectional"))
      (node (ref "C10") (pin "1") (pinfunction "1_1") (pintype "passive"))
      (node (ref "R56") (pin "1") (pinfunction "1_1") (pintype "passive"))
      (node (ref "SPI_JUMPERS") (pin "2") (pinfunction "2_2") (pintype "passive"))
    )
    (net (code "63") (name "/RI") (class "Default")
      (node (ref "FTDI") (pin "6") (pinfunction "~{RI}_6") (pintype "input"))
      (node (ref "JP16") (pin "1") (pinfunction "1_1") (pintype "passive"))
    )
    (net (code "64") (name "/RTS") (class "Default")
      (node (ref "FTDI") (pin "3") (pinfunction "~{RTS}_3") (pintype "output"))
      (node (ref "JP9") (pin "1") (pinfunction "1_1") (pintype "passive"))
    )
    (net (code "65") (name "/RXD") (class "Default")
      (node (ref "ATMEGA328P") (pin "30") (pinfunction "PD0_30") (pintype "bidirectional"))
      (node (ref "FTDI") (pin "1") (pinfunction "TXD_1") (pintype "output"))
    )
    (net (code "66") (name "/STOP{slash}RESET") (class "Default")
      (node (ref "EXPANDER") (pin "5") (pinfunction "P1_5") (pintype "bidirectional"))
      (node (ref "FFC_CON") (pin "11") (pinfunction "1_11") (pintype "passive"))
      (node (ref "R45") (pin "2") (pinfunction "2_2") (pintype "passive"))
    )
    (net (code "67") (name "/S_VCC") (class "Default")
      (node (ref "ATMEGA328P") (pin "11") (pinfunction "PD7_11") (pintype "bidirectional"))
      (node (ref "ATMEGA328P") (pin "4") (pinfunction "VCC_2_4") (pintype "power_in"))
      (node (ref "ATMEGA328P") (pin "6") (pinfunction "VCC_6") (pintype "power_in"))
      (node (ref "C31") (pin "+") (pinfunction "+_+") (pintype "passive"))
      (node (ref "L1") (pin "1") (pinfunction "1_1") (pintype "passive"))
      (node (ref "SHOTTKY") (pin "C") (pinfunction "C_C") (pintype "passive"))
      (node (ref "SPI_JUMPERS") (pin "5") (pinfunction "5_5") (pintype "passive"))
    )
    (net (code "68") (name "/TXD") (class "Default")
      (node (ref "ATMEGA328P") (pin "31") (pinfunction "PD1_31") (pintype "bidirectional"))
      (node (ref "FTDI") (pin "5") (pinfunction "RXD_5") (pintype "input"))
    )
    (net (code "69") (name "/UA1") (class "Default")
      (node (ref "ATMEGA328P") (pin "1") (pinfunction "PD3_1") (pintype "bidirectional"))
      (node (ref "JP1") (pin "1") (pinfunction "1_1") (pintype "passive"))
    )
    (net (code "70") (name "/UA2") (class "Default")
      (node (ref "ATMEGA328P") (pin "2") (pinfunction "PD4_2") (pintype "bidirectional"))
      (node (ref "JP2") (pin "1") (pinfunction "1_1") (pintype "passive"))
    )
    (net (code "71") (name "/UA3") (class "Default")
      (node (ref "ATMEGA328P") (pin "9") (pinfunction "PD5_9") (pintype "bidirectional"))
      (node (ref "JP3") (pin "1") (pinfunction "1_1") (pintype "passive"))
    )
    (net (code "72") (name "/UA4") (class "Default")
      (node (ref "ATMEGA328P") (pin "19") (pinfunction "ADC6_19") (pintype "input"))
      (node (ref "JP4") (pin "1") (pinfunction "1_1") (pintype "passive"))
    )
    (net (code "73") (name "/UA5") (class "Default")
      (node (ref "ATMEGA328P") (pin "22") (pinfunction "ADC7_22") (pintype "input"))
      (node (ref "JP5") (pin "1") (pinfunction "1_1") (pintype "passive"))
    )
    (net (code "74") (name "/UD1") (class "Default")
      (node (ref "JP13") (pin "1") (pinfunction "1_1") (pintype "passive"))
      (node (ref "LS_SEC_REG") (pin "3") (pinfunction "Q0_3") (pintype "open_collector"))
    )
    (net (code "75") (name "/UD2") (class "Default")
      (node (ref "JP14") (pin "1") (pinfunction "1_1") (pintype "passive"))
      (node (ref "MS_MIN_REG") (pin "3") (pinfunction "Q0_3") (pintype "open_collector"))
    )
    (net (code "76") (name "/UP1") (class "Default")
      (node (ref "EXPANDER") (pin "12") (pinfunction "P7_12") (pintype "bidirectional"))
      (node (ref "JP6") (pin "1") (pinfunction "1_1") (pintype "passive"))
      (node (ref "R61") (pin "2") (pinfunction "2_2") (pintype "passive"))
    )
    (net (code "77") (name "/USBDM") (class "Default")
      (node (ref "FFC_CON") (pin "2") (pinfunction "1_2") (pintype "passive"))
      (node (ref "FTDI") (pin "16") (pinfunction "USBDM_16") (pintype "bidirectional"))
    )
    (net (code "78") (name "/USBDP") (class "Default")
      (node (ref "FFC_CON") (pin "1") (pinfunction "1_1") (pintype "passive"))
      (node (ref "FTDI") (pin "15") (pinfunction "USBDP_15") (pintype "bidirectional"))
    )
    (net (code "79") (name "/VOLUME") (class "Default")
      (node (ref "EXPANDER") (pin "6") (pinfunction "P2_6") (pintype "bidirectional"))
      (node (ref "FFC_CON") (pin "10") (pinfunction "1_10") (pintype "passive"))
      (node (ref "R44") (pin "2") (pinfunction "2_2") (pintype "passive"))
    )
    (net (code "80") (name "/WARNING") (class "Default")
      (node (ref "EXPANDER") (pin "7") (pinfunction "P3_7") (pintype "bidirectional"))
      (node (ref "FFC_CON") (pin "9") (pinfunction "1_9") (pintype "passive"))
      (node (ref "R43") (pin "2") (pinfunction "2_2") (pintype "passive"))
    )
    (net (code "81") (name "/XTAL1") (class "Default")
      (node (ref "ATMEGA328P") (pin "7") (pinfunction "PB6_7") (pintype "bidirectional"))
      (node (ref "C29") (pin "2") (pinfunction "2_2") (pintype "passive"))
      (node (ref "QUARTZ") (pin "X2") (pinfunction "2_X2") (pintype "passive"))
    )
    (net (code "82") (name "/XTAL2") (class "Default")
      (node (ref "ATMEGA328P") (pin "8") (pinfunction "PB7_8") (pintype "bidirectional"))
      (node (ref "C30") (pin "2") (pinfunction "2_2") (pintype "passive"))
      (node (ref "QUARTZ") (pin "X1") (pinfunction "1_X1") (pintype "passive"))
    )
    (net (code "83") (name "GND") (class "Default")
      (node (ref "ATMEGA328P") (pin "21") (pinfunction "GND_21") (pintype "passive"))
      (node (ref "ATMEGA328P") (pin "3") (pinfunction "GND_2_3") (pintype "passive"))
      (node (ref "ATMEGA328P") (pin "5") (pinfunction "GND_3_5") (pintype "passive"))
      (node (ref "BATTERY_CON") (pin "3") (pinfunction "S_3") (pintype "passive"))
      (node (ref "C1") (pin "1") (pinfunction "1_1") (pintype "passive"))
      (node (ref "C14") (pin "1") (pinfunction "1_1") (pintype "passive"))
      (node (ref "C15") (pin "1") (pinfunction "1_1") (pintype "passive"))
      (node (ref "C16") (pin "1") (pinfunction "1_1") (pintype "passive"))
      (node (ref "C17") (pin "1") (pinfunction "1_1") (pintype "passive"))
      (node (ref "C18") (pin "1") (pinfunction "1_1") (pintype "passive"))
      (node (ref "C2") (pin "1") (pinfunction "1_1") (pintype "passive"))
      (node (ref "C29") (pin "1") (pinfunction "1_1") (pintype "passive"))
      (node (ref "C3") (pin "-") (pinfunction "-_-") (pintype "passive"))
      (node (ref "C30") (pin "1") (pinfunction "1_1") (pintype "passive"))
      (node (ref "C31") (pin "-") (pinfunction "-_-") (pintype "passive"))
      (node (ref "C32") (pin "2") (pinfunction "2_2") (pintype "passive"))
      (node (ref "C4") (pin "2") (pinfunction "2_2") (pintype "passive"))
      (node (ref "C5") (pin "2") (pinfunction "2_2") (pintype "passive"))
      (node (ref "C6") (pin "1") (pinfunction "1_1") (pintype "passive"))
      (node (ref "C7") (pin "2") (pinfunction "2_2") (pintype "passive"))
      (node (ref "C8") (pin "1") (pinfunction "1_1") (pintype "passive"))
      (node (ref "CHARGER") (pin "1") (pinfunction "TEMP_1") (pintype "bidirectional"))
      (node (ref "CHARGER") (pin "3") (pinfunction "GND_3") (pintype "bidirectional"))
      (node (ref "CHARGER") (pin "ETP") (pinfunction "GND_ETP") (pintype "bidirectional"))
      (node (ref "EXPANDER") (pin "1") (pinfunction "A0_1") (pintype "input"))
      (node (ref "EXPANDER") (pin "2") (pinfunction "A1_2") (pintype "input"))
      (node (ref "EXPANDER") (pin "3") (pinfunction "A2_3") (pintype "input"))
      (node (ref "EXPANDER") (pin "8") (pinfunction "VSS_8") (pintype "power_in"))
      (node (ref "FTDI") (pin "18") (pinfunction "GND_18") (pintype "power_in"))
      (node (ref "FTDI") (pin "21") (pinfunction "GND_21") (pintype "power_in"))
      (node (ref "FTDI") (pin "25") (pinfunction "GND_25") (pintype "power_in"))
      (node (ref "FTDI") (pin "26") (pinfunction "TEST_26") (pintype "input"))
      (node (ref "FTDI") (pin "7") (pinfunction "GND_7") (pintype "power_in"))
      (node (ref "J_REG_9V_1") (pin "GND") (pinfunction "GND_GND") (pintype "bidirectional"))
      (node (ref "LDO_5V") (pin "1") (pinfunction "GND_1") (pintype "input"))
      (node (ref "LS_MIN_REG") (pin "16") (pinfunction "GND_16") (pintype "power_in"))
      (node (ref "LS_SEC_REG") (pin "16") (pinfunction "GND_16") (pintype "power_in"))
      (node (ref "MS_MIN_REG") (pin "16") (pinfunction "GND_16") (pintype "power_in"))
      (node (ref "MS_SEC_REG") (pin "16") (pinfunction "GND_16") (pintype "power_in"))
      (node (ref "NPN_AMP") (pin "2") (pinfunction "E_2") (pintype "passive"))
      (node (ref "PHOTORES") (pin "1") (pinfunction "1_1") (pintype "passive"))
      (node (ref "POWER_CON") (pin "2") (pinfunction "S_2") (pintype "passive"))
      (node (ref "QUARTZ") (pin "SHEILD") (pinfunction "GND_SHEILD") (pintype "power_in"))
      (node (ref "R48") (pin "2") (pinfunction "2_2") (pintype "passive"))
      (node (ref "SPI_JUMPERS") (pin "1") (pinfunction "1_1") (pintype "passive"))
      (node (ref "SWITCH") (pin "3") (pinfunction "P$3_3") (pintype "bidirectional"))
      (node (ref "SWITCH") (pin "6") (pinfunction "P$3_6") (pintype "bidirectional"))
      (node (ref "SWITCH") (pin "CASE1") (pinfunction "P$1_CASE1") (pintype "bidirectional"))
      (node (ref "SWITCH") (pin "CASE2") (pinfunction "P$1_CASE2") (pintype "bidirectional"))
    )
    (net (code "84") (name "Net-(CHARGER-CHRG)") (class "Default")
      (node (ref "CHARGER") (pin "7") (pinfunction "CHRG_7") (pintype "bidirectional"))
      (node (ref "R39") (pin "2") (pinfunction "2_2") (pintype "passive"))
    )
    (net (code "85") (name "Net-(CHARGER-PROG)") (class "Default")
      (node (ref "CHARGER") (pin "2") (pinfunction "PROG_2") (pintype "bidirectional"))
      (node (ref "R48") (pin "1") (pinfunction "1_1") (pintype "passive"))
    )
    (net (code "86") (name "Net-(CHARGER-STDBY)") (class "Default")
      (node (ref "CHARGER") (pin "6") (pinfunction "STDBY_6") (pintype "bidirectional"))
      (node (ref "R40") (pin "2") (pinfunction "2_2") (pintype "passive"))
    )
    (net (code "87") (name "Net-(CHRG_LED-PadC)") (class "Default")
      (node (ref "CHRG_LED") (pin "C") (pinfunction "C_C") (pintype "passive"))
      (node (ref "R39") (pin "1") (pinfunction "1_1") (pintype "passive"))
    )
    (net (code "88") (name "Net-(COLON1-PadA)") (class "Default")
      (node (ref "COLON1") (pin "A") (pinfunction "A_A") (pintype "passive"))
      (node (ref "R50") (pin "2") (pinfunction "2_2") (pintype "passive"))
    )
    (net (code "89") (name "Net-(COLON2-PadA)") (class "Default")
      (node (ref "COLON2") (pin "A") (pinfunction "A_A") (pintype "passive"))
      (node (ref "R34") (pin "2") (pinfunction "2_2") (pintype "passive"))
    )
    (net (code "90") (name "Net-(FFC_CONF-1)") (class "Default")
      (node (ref "FFC_CON") (pin "3") (pinfunction "1_3") (pintype "passive"))
      (node (ref "R64") (pin "1") (pinfunction "1_1") (pintype "passive"))
    )
    (net (code "91") (name "Net-(FFC_CONG-1)") (class "Default")
      (node (ref "FFC_CON") (pin "4") (pinfunction "1_4") (pintype "passive"))
      (node (ref "R47") (pin "1") (pinfunction "1_1") (pintype "passive"))
    )
    (net (code "92") (name "Net-(FFC_CONH-1)") (class "Default")
      (node (ref "FFC_CON") (pin "5") (pinfunction "1_5") (pintype "passive"))
      (node (ref "R52") (pin "1") (pinfunction "1_1") (pintype "passive"))
    )
    (net (code "93") (name "Net-(FTDI-3V3OUT)") (class "Default")
      (node (ref "C1") (pin "2") (pinfunction "2_2") (pintype "passive"))
      (node (ref "FTDI") (pin "17") (pinfunction "3V3OUT_17") (pintype "output"))
    )
    (net (code "94") (name "Net-(FTDI-CBUS0)") (class "Default")
      (node (ref "FTDI") (pin "23") (pinfunction "CBUS0_23") (pintype "bidirectional"))
      (node (ref "R66") (pin "2") (pinfunction "2_2") (pintype "passive"))
    )
    (net (code "95") (name "Net-(FTDI-CBUS1)") (class "Default")
      (node (ref "FTDI") (pin "22") (pinfunction "CBUS1_22") (pintype "bidirectional"))
      (node (ref "R65") (pin "2") (pinfunction "2_2") (pintype "passive"))
    )
    (net (code "96") (name "Net-(FTDI-~{DTR})") (class "Default")
      (node (ref "C10") (pin "2") (pinfunction "2_2") (pintype "passive"))
      (node (ref "FTDI") (pin "2") (pinfunction "~{DTR}_2") (pintype "output"))
    )
    (net (code "97") (name "Net-(LSDIGIT_MINUTES-PadA)") (class "Default")
      (node (ref "LSDIGIT_MINUTES") (pin "A") (pinfunction "A_A") (pintype "passive"))
      (node (ref "R7") (pin "1") (pinfunction "1_1") (pintype "passive"))
    )
    (net (code "98") (name "Net-(LSDIGIT_MINUTES-PadB)") (class "Default")
      (node (ref "LSDIGIT_MINUTES") (pin "B") (pinfunction "B_B") (pintype "passive"))
      (node (ref "R6") (pin "1") (pinfunction "1_1") (pintype "passive"))
    )
    (net (code "99") (name "Net-(LSDIGIT_MINUTES-PadC)") (class "Default")
      (node (ref "LSDIGIT_MINUTES") (pin "C") (pinfunction "C_C") (pintype "passive"))
      (node (ref "R5") (pin "1") (pinfunction "1_1") (pintype "passive"))
    )
    (net (code "100") (name "Net-(LSDIGIT_MINUTES-PadD)") (class "Default")
      (node (ref "LSDIGIT_MINUTES") (pin "D") (pinfunction "D_D") (pintype "passive"))
      (node (ref "R4") (pin "1") (pinfunction "1_1") (pintype "passive"))
    )
    (net (code "101") (name "Net-(LSDIGIT_MINUTES-PadE)") (class "Default")
      (node (ref "LSDIGIT_MINUTES") (pin "E") (pinfunction "E_E") (pintype "passive"))
      (node (ref "R3") (pin "1") (pinfunction "1_1") (pintype "passive"))
    )
    (net (code "102") (name "Net-(LSDIGIT_MINUTES-PadF)") (class "Default")
      (node (ref "LSDIGIT_MINUTES") (pin "F") (pinfunction "F_F") (pintype "passive"))
      (node (ref "R2") (pin "1") (pinfunction "1_1") (pintype "passive"))
    )
    (net (code "103") (name "Net-(LSDIGIT_MINUTES-PadG)") (class "Default")
      (node (ref "LSDIGIT_MINUTES") (pin "G") (pinfunction "G_G") (pintype "passive"))
      (node (ref "R1") (pin "1") (pinfunction "1_1") (pintype "passive"))
    )
    (net (code "104") (name "Net-(LSDIGIT_SECONDS-PadA)") (class "Default")
      (node (ref "LSDIGIT_SECONDS") (pin "A") (pinfunction "A_A") (pintype "passive"))
      (node (ref "R21") (pin "1") (pinfunction "1_1") (pintype "passive"))
    )
    (net (code "105") (name "Net-(LSDIGIT_SECONDS-PadB)") (class "Default")
      (node (ref "LSDIGIT_SECONDS") (pin "B") (pinfunction "B_B") (pintype "passive"))
      (node (ref "R20") (pin "1") (pinfunction "1_1") (pintype "passive"))
    )
    (net (code "106") (name "Net-(LSDIGIT_SECONDS-PadC)") (class "Default")
      (node (ref "LSDIGIT_SECONDS") (pin "C") (pinfunction "C_C") (pintype "passive"))
      (node (ref "R19") (pin "1") (pinfunction "1_1") (pintype "passive"))
    )
    (net (code "107") (name "Net-(LSDIGIT_SECONDS-PadD)") (class "Default")
      (node (ref "LSDIGIT_SECONDS") (pin "D") (pinfunction "D_D") (pintype "passive"))
      (node (ref "R18") (pin "1") (pinfunction "1_1") (pintype "passive"))
    )
    (net (code "108") (name "Net-(LSDIGIT_SECONDS-PadE)") (class "Default")
      (node (ref "LSDIGIT_SECONDS") (pin "E") (pinfunction "E_E") (pintype "passive"))
      (node (ref "R17") (pin "1") (pinfunction "1_1") (pintype "passive"))
    )
    (net (code "109") (name "Net-(LSDIGIT_SECONDS-PadF)") (class "Default")
      (node (ref "LSDIGIT_SECONDS") (pin "F") (pinfunction "F_F") (pintype "passive"))
      (node (ref "R16") (pin "1") (pinfunction "1_1") (pintype "passive"))
    )
    (net (code "110") (name "Net-(LSDIGIT_SECONDS-PadG)") (class "Default")
      (node (ref "LSDIGIT_SECONDS") (pin "G") (pinfunction "G_G") (pintype "passive"))
      (node (ref "R15") (pin "1") (pinfunction "1_1") (pintype "passive"))
    )
    (net (code "111") (name "Net-(LS_MIN_REGA-DI)") (class "Default")
      (node (ref "LS_MIN_REG") (pin "2") (pinfunction "DI_2") (pintype "input"))
      (node (ref "MS_SEC_REG") (pin "9") (pinfunction "DO_9") (pintype "output"))
    )
    (net (code "112") (name "Net-(LS_MIN_REGA-DO)") (class "Default")
      (node (ref "LS_MIN_REG") (pin "9") (pinfunction "DO_9") (pintype "output"))
      (node (ref "MS_MIN_REG") (pin "2") (pinfunction "DI_2") (pintype "input"))
    )
    (net (code "113") (name "Net-(LS_MIN_REGA-SCLR)") (class "Default")
      (node (ref "LS_MIN_REG") (pin "7") (pinfunction "SCLR_7") (pintype "input"))
      (node (ref "LS_SEC_REG") (pin "7") (pinfunction "SCLR_7") (pintype "input"))
      (node (ref "MS_MIN_REG") (pin "7") (pinfunction "SCLR_7") (pintype "input"))
      (node (ref "MS_SEC_REG") (pin "7") (pinfunction "SCLR_7") (pintype "input"))
      (node (ref "R29") (pin "1") (pinfunction "1_1") (pintype "passive"))
    )
    (net (code "114") (name "Net-(LS_SEC_REGA-DO)") (class "Default")
      (node (ref "LS_SEC_REG") (pin "9") (pinfunction "DO_9") (pintype "output"))
      (node (ref "MS_SEC_REG") (pin "2") (pinfunction "DI_2") (pintype "input"))
    )
    (net (code "115") (name "Net-(MSDIGIT_MINUTES-PadA)") (class "Default")
      (node (ref "MSDIGIT_MINUTES") (pin "A") (pinfunction "A_A") (pintype "passive"))
      (node (ref "R27") (pin "1") (pinfunction "1_1") (pintype "passive"))
    )
    (net (code "116") (name "Net-(MSDIGIT_MINUTES-PadB)") (class "Default")
      (node (ref "MSDIGIT_MINUTES") (pin "B") (pinfunction "B_B") (pintype "passive"))
      (node (ref "R26") (pin "1") (pinfunction "1_1") (pintype "passive"))
    )
    (net (code "117") (name "Net-(MSDIGIT_MINUTES-PadC)") (class "Default")
      (node (ref "MSDIGIT_MINUTES") (pin "C") (pinfunction "C_C") (pintype "passive"))
      (node (ref "R25") (pin "1") (pinfunction "1_1") (pintype "passive"))
    )
    (net (code "118") (name "Net-(MSDIGIT_MINUTES-PadD)") (class "Default")
      (node (ref "MSDIGIT_MINUTES") (pin "D") (pinfunction "D_D") (pintype "passive"))
      (node (ref "R24") (pin "1") (pinfunction "1_1") (pintype "passive"))
    )
    (net (code "119") (name "Net-(MSDIGIT_MINUTES-PadE)") (class "Default")
      (node (ref "MSDIGIT_MINUTES") (pin "E") (pinfunction "E_E") (pintype "passive"))
      (node (ref "R23") (pin "1") (pinfunction "1_1") (pintype "passive"))
    )
    (net (code "120") (name "Net-(MSDIGIT_MINUTES-PadF)") (class "Default")
      (node (ref "MSDIGIT_MINUTES") (pin "F") (pinfunction "F_F") (pintype "passive"))
      (node (ref "R22") (pin "1") (pinfunction "1_1") (pintype "passive"))
    )
    (net (code "121") (name "Net-(MSDIGIT_MINUTES-PadG)") (class "Default")
      (node (ref "MSDIGIT_MINUTES") (pin "G") (pinfunction "G_G") (pintype "passive"))
      (node (ref "R28") (pin "1") (pinfunction "1_1") (pintype "passive"))
    )
    (net (code "122") (name "Net-(MSDIGIT_SECONDS-PadA)") (class "Default")
      (node (ref "MSDIGIT_SECONDS") (pin "A") (pinfunction "A_A") (pintype "passive"))
      (node (ref "R14") (pin "1") (pinfunction "1_1") (pintype "passive"))
    )
    (net (code "123") (name "Net-(MSDIGIT_SECONDS-PadB)") (class "Default")
      (node (ref "MSDIGIT_SECONDS") (pin "B") (pinfunction "B_B") (pintype "passive"))
      (node (ref "R13") (pin "1") (pinfunction "1_1") (pintype "passive"))
    )
    (net (code "124") (name "Net-(MSDIGIT_SECONDS-PadC)") (class "Default")
      (node (ref "MSDIGIT_SECONDS") (pin "C") (pinfunction "C_C") (pintype "passive"))
      (node (ref "R12") (pin "1") (pinfunction "1_1") (pintype "passive"))
    )
    (net (code "125") (name "Net-(MSDIGIT_SECONDS-PadD)") (class "Default")
      (node (ref "MSDIGIT_SECONDS") (pin "D") (pinfunction "D_D") (pintype "passive"))
      (node (ref "R11") (pin "1") (pinfunction "1_1") (pintype "passive"))
    )
    (net (code "126") (name "Net-(MSDIGIT_SECONDS-PadE)") (class "Default")
      (node (ref "MSDIGIT_SECONDS") (pin "E") (pinfunction "E_E") (pintype "passive"))
      (node (ref "R10") (pin "1") (pinfunction "1_1") (pintype "passive"))
    )
    (net (code "127") (name "Net-(MSDIGIT_SECONDS-PadF)") (class "Default")
      (node (ref "MSDIGIT_SECONDS") (pin "F") (pinfunction "F_F") (pintype "passive"))
      (node (ref "R9") (pin "1") (pinfunction "1_1") (pintype "passive"))
    )
    (net (code "128") (name "Net-(MSDIGIT_SECONDS-PadG)") (class "Default")
      (node (ref "MSDIGIT_SECONDS") (pin "G") (pinfunction "G_G") (pintype "passive"))
      (node (ref "R8") (pin "1") (pinfunction "1_1") (pintype "passive"))
    )
    (net (code "129") (name "Net-(NPN_AMP-B)") (class "Default")
      (node (ref "NPN_AMP") (pin "1") (pinfunction "B_1") (pintype "passive"))
      (node (ref "R30") (pin "1") (pinfunction "1_1") (pintype "passive"))
    )
    (net (code "130") (name "Net-(NPN_AMP-C)") (class "Default")
      (node (ref "BUZZER") (pin "2") (pinfunction "2_2") (pintype "passive"))
      (node (ref "NPN_AMP") (pin "3") (pinfunction "C_3") (pintype "passive"))
    )
    (net (code "131") (name "Net-(R32-Pad2)") (class "Default")
      (node (ref "R32") (pin "2") (pinfunction "2_2") (pintype "passive"))
      (node (ref "R50") (pin "1") (pinfunction "1_1") (pintype "passive"))
    )
    (net (code "132") (name "Net-(R34-Pad1)") (class "Default")
      (node (ref "R34") (pin "1") (pinfunction "1_1") (pintype "passive"))
      (node (ref "R35") (pin "2") (pinfunction "2_2") (pintype "passive"))
    )
    (net (code "133") (name "Net-(R40-Pad1)") (class "Default")
      (node (ref "R40") (pin "1") (pinfunction "1_1") (pintype "passive"))
      (node (ref "STDBY_LED") (pin "C") (pinfunction "C_C") (pintype "passive"))
    )
    (net (code "134") (name "Net-(R65-Pad1)") (class "Default")
      (node (ref "R65") (pin "1") (pinfunction "1_1") (pintype "passive"))
      (node (ref "RXLED") (pin "C") (pinfunction "C_C") (pintype "passive"))
    )
    (net (code "135") (name "Net-(R66-Pad1)") (class "Default")
      (node (ref "R66") (pin "1") (pinfunction "1_1") (pintype "passive"))
      (node (ref "TXLED") (pin "C") (pinfunction "C_C") (pintype "passive"))
    )
    (net (code "136") (name "Net-(SWITCHC-P$2)") (class "Default")
      (node (ref "J_REG_9V_1") (pin "VIN") (pinfunction "VIN_VIN") (pintype "bidirectional"))
      (node (ref "SWITCH") (pin "2") (pinfunction "P$2_2") (pintype "bidirectional"))
      (node (ref "SWITCH") (pin "5") (pinfunction "P$2_5") (pintype "bidirectional"))
    )
    (net (code "137") (name "VCC") (class "Default")
      (node (ref "ATMEGA328P") (pin "10") (pinfunction "PD6_10") (pintype "bidirectional"))
      (node (ref "BUZZER") (pin "1") (pinfunction "1_1") (pintype "passive"))
      (node (ref "C14") (pin "2") (pinfunction "2_2") (pintype "passive"))
      (node (ref "C15") (pin "2") (pinfunction "2_2") (pintype "passive"))
      (node (ref "C16") (pin "2") (pinfunction "2_2") (pintype "passive"))
      (node (ref "C17") (pin "2") (pinfunction "2_2") (pintype "passive"))
      (node (ref "C18") (pin "2") (pinfunction "2_2") (pintype "passive"))
      (node (ref "C7") (pin "1") (pinfunction "1_1") (pintype "passive"))
      (node (ref "EXPANDER") (pin "16") (pinfunction "VDD_16") (pintype "power_in"))
      (node (ref "LDO_5V") (pin "2") (pinfunction "OUT_2") (pintype "passive"))
      (node (ref "LDO_5V") (pin "4") (pinfunction "OUT_4") (pintype "passive"))
      (node (ref "LS_MIN_REG") (pin "1") (pinfunction "VCC_1") (pintype "power_in"))
      (node (ref "LS_SEC_REG") (pin "1") (pinfunction "VCC_1") (pintype "power_in"))
      (node (ref "MS_MIN_REG") (pin "1") (pinfunction "VCC_1") (pintype "power_in"))
      (node (ref "MS_SEC_REG") (pin "1") (pinfunction "VCC_1") (pintype "power_in"))
      (node (ref "POWER_CON") (pin "3") (pinfunction "S_3") (pintype "passive"))
      (node (ref "R29") (pin "2") (pinfunction "2_2") (pintype "passive"))
      (node (ref "R31") (pin "1") (pinfunction "1_1") (pintype "passive"))
      (node (ref "R32") (pin "1") (pinfunction "1_1") (pintype "passive"))
      (node (ref "R33") (pin "1") (pinfunction "1_1") (pintype "passive"))
      (node (ref "R35") (pin "1") (pinfunction "1_1") (pintype "passive"))
      (node (ref "R36") (pin "2") (pinfunction "2_2") (pintype "passive"))
      (node (ref "R42") (pin "1") (pinfunction "1_1") (pintype "passive"))
      (node (ref "R43") (pin "1") (pinfunction "1_1") (pintype "passive"))
      (node (ref "R44") (pin "1") (pinfunction "1_1") (pintype "passive"))
      (node (ref "R45") (pin "1") (pinfunction "1_1") (pintype "passive"))
      (node (ref "R46") (pin "1") (pinfunction "1_1") (pintype "passive"))
      (node (ref "R56") (pin "2") (pinfunction "2_2") (pintype "passive"))
      (node (ref "R61") (pin "1") (pinfunction "1_1") (pintype "passive"))
      (node (ref "SHOTTKY") (pin "A") (pinfunction "A_A") (pintype "passive"))
    )
    (net (code "138") (name "unconnected-(FTDI-OSCI-Pad27)") (class "Default")
      (node (ref "FTDI") (pin "27") (pinfunction "OSCI_27") (pintype "input"))
    )
    (net (code "139") (name "unconnected-(LSDIGIT_MINUTES-PadDP)") (class "Default")
      (node (ref "LSDIGIT_MINUTES") (pin "DP") (pinfunction "DP_DP") (pintype "passive"))
    )
    (net (code "140") (name "unconnected-(LSDIGIT_SECONDS-PadDP)") (class "Default")
      (node (ref "LSDIGIT_SECONDS") (pin "DP") (pinfunction "DP_DP") (pintype "passive"))
    )
    (net (code "141") (name "unconnected-(MSDIGIT_MINUTES-PadDP)") (class "Default")
      (node (ref "MSDIGIT_MINUTES") (pin "DP") (pinfunction "DP_DP") (pintype "passive"))
    )
    (net (code "142") (name "unconnected-(MSDIGIT_SECONDS-PadDP)") (class "Default")
      (node (ref "MSDIGIT_SECONDS") (pin "DP") (pinfunction "DP_DP") (pintype "passive"))
    )
    (net (code "143") (name "unconnected-(MS_MIN_REGA-DO-Pad9)") (class "Default")
      (node (ref "MS_MIN_REG") (pin "9") (pinfunction "DO_9") (pintype "output"))
    )
    (net (code "144") (name "unconnected-(POTENTIOMETER-E-Pad3)") (class "Default")
      (node (ref "POTENTIOMETER") (pin "3") (pinfunction "E_3") (pintype "passive"))
    )
  )
)
